# design.net
KiCad netlist of a schematic drawn in Altium Designer
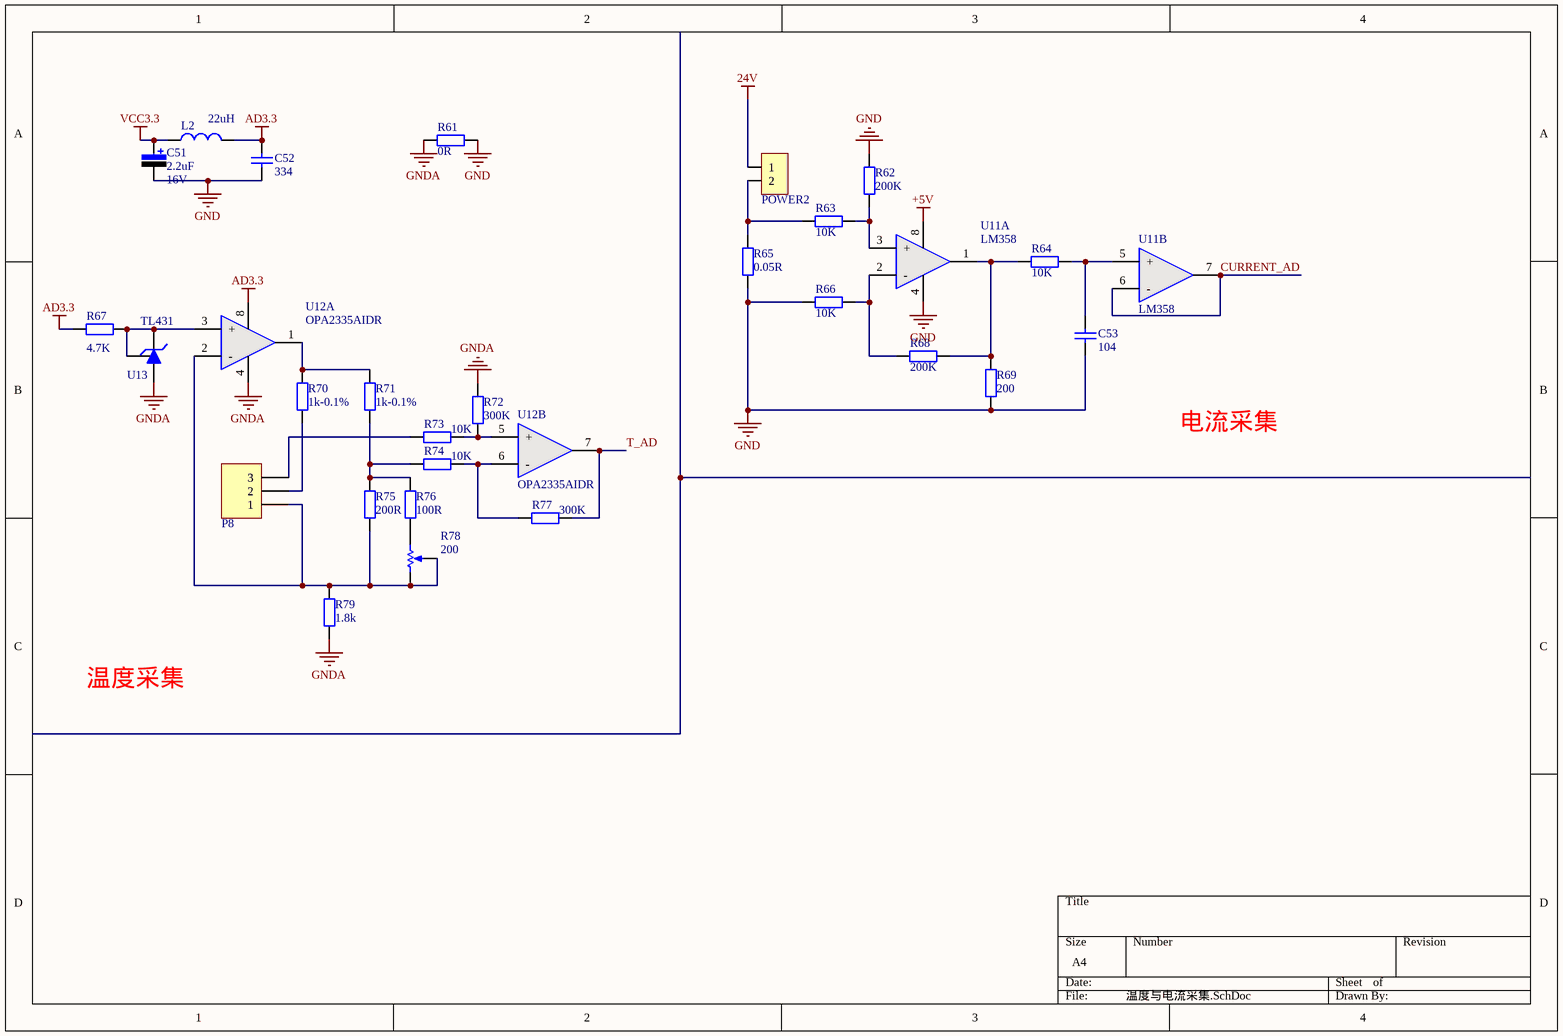
[diagram p0: 温度与电流采集.SchDoc]

(export (version "E")
  (design (tool "Eeschema 10.0.6"))
  (components
    (comp (ref "C51")
      (value "2.2uF")
      (footprint "CAP-3216")
      (description "极性电解电容")
      (fields
        (field (name "VOL") "16V")
        (field (name "Comment") "Cap Pol")
        (field (name "PUBLISHER") "Altium Limited")
      )
      (libsource (lib "Fszhang") (part "Cap Pol"))
    )
    (comp (ref "C52")
      (value "334")
      (footprint "C-RAD-0603")
      (description "无极性电容")
      (fields (field (name "Comment") "Cap") (field (name "PUBLISHER") "Altium Limited"))
      (libsource (lib "Fszhang") (part "Cap"))
    )
    (comp (ref "C53")
      (value "104")
      (footprint "C-RAD-0603")
      (description "无极性电容")
      (fields (field (name "Comment") "Cap") (field (name "PUBLISHER") "Altium Limited"))
      (libsource (lib "Fszhang") (part "Cap"))
    )
    (comp (ref "L2")
      (value "22uH")
      (footprint "0805-1")
      (description "电感")
      (fields (field (name "Comment") "Inductor") (field (name "PUBLISHER") "Altium Limited"))
      (libsource (lib "Fszhang") (part "Inductor"))
    )
    (comp (ref "P8")
      (value "Header 3")
      (footprint "XH2.54*3卧贴")
      (description "接插件")
      (fields (field (name "PUBLISHER") "Altium Limited"))
      (libsource (lib "Fszhang") (part "Header 3"))
    )
    (comp (ref "POWER2")
      (value "CNT5.08MM*2 WAN")
      (footprint "CNT5.08*2WAN")
      (libsource (lib "MY_Library") (part "CNT5.08MM*2 WAN"))
    )
    (comp (ref "R61")
      (value "0R")
      (footprint "0603-1")
      (description "贴片电阻")
      (fields (field (name "Comment") "Res1") (field (name "PUBLISHER") "Altium Limited"))
      (libsource (lib "") (part "Res1_2"))
    )
    (comp (ref "R62")
      (value "200K")
      (footprint "0603-1")
      (description "贴片电阻")
      (fields (field (name "Comment") "Res1") (field (name "PUBLISHER") "Altium Limited"))
      (libsource (lib "Fszhang") (part "Res1"))
    )
    (comp (ref "R63")
      (value "10K")
      (footprint "0603-1")
      (description "贴片电阻")
      (fields (field (name "Comment") "Res1") (field (name "PUBLISHER") "Altium Limited"))
      (libsource (lib "") (part "Res1_1"))
    )
    (comp (ref "R64")
      (value "10K")
      (footprint "0603-1")
      (description "贴片电阻")
      (fields (field (name "Comment") "Res1") (field (name "PUBLISHER") "Altium Limited"))
      (libsource (lib "") (part "Res1_2"))
    )
    (comp (ref "R65")
      (value "0.05R")
      (footprint "1*8*50mR")
      (description "贴片电阻")
      (fields (field (name "Comment") "Res1") (field (name "PUBLISHER") "Altium Limited"))
      (libsource (lib "Fszhang") (part "Res1"))
    )
    (comp (ref "R66")
      (value "10K")
      (footprint "0603-1")
      (description "贴片电阻")
      (fields (field (name "Comment") "Res1") (field (name "PUBLISHER") "Altium Limited"))
      (libsource (lib "") (part "Res1_1"))
    )
    (comp (ref "R67")
      (value "4.7K")
      (footprint "0603-1")
      (description "贴片电阻")
      (fields (field (name "Comment") "Res1") (field (name "PUBLISHER") "Altium Limited"))
      (libsource (lib "") (part "Res1_1"))
    )
    (comp (ref "R68")
      (value "200K")
      (footprint "0603-1")
      (description "贴片电阻")
      (fields (field (name "Comment") "Res1") (field (name "PUBLISHER") "Altium Limited"))
      (libsource (lib "") (part "Res1_2"))
    )
    (comp (ref "R69")
      (value "200")
      (footprint "0603-1")
      (description "贴片电阻")
      (fields (field (name "Comment") "Res1") (field (name "PUBLISHER") "Altium Limited"))
      (libsource (lib "Fszhang") (part "Res1"))
    )
    (comp (ref "R70")
      (value "1k-0.1%")
      (footprint "0603-1")
      (description "贴片电阻")
      (fields (field (name "Comment") "Res1") (field (name "PUBLISHER") "Altium Limited"))
      (libsource (lib "Fszhang") (part "Res1"))
    )
    (comp (ref "R71")
      (value "1k-0.1%")
      (footprint "0603-1")
      (description "贴片电阻")
      (fields (field (name "Comment") "Res1") (field (name "PUBLISHER") "Altium Limited"))
      (libsource (lib "Fszhang") (part "Res1"))
    )
    (comp (ref "R72")
      (value "300K")
      (footprint "0603-1")
      (description "贴片电阻")
      (fields (field (name "Comment") "Res1") (field (name "PUBLISHER") "Altium Limited"))
      (libsource (lib "Fszhang") (part "Res1"))
    )
    (comp (ref "R73")
      (value "10K")
      (footprint "0603-1")
      (description "贴片电阻")
      (fields (field (name "Comment") "Res1") (field (name "PUBLISHER") "Altium Limited"))
      (libsource (lib "") (part "Res1_1"))
    )
    (comp (ref "R74")
      (value "10K")
      (footprint "0603-1")
      (description "贴片电阻")
      (fields (field (name "Comment") "Res1") (field (name "PUBLISHER") "Altium Limited"))
      (libsource (lib "") (part "Res1_1"))
    )
    (comp (ref "R75")
      (value "200R")
      (footprint "0603-1")
      (description "贴片电阻")
      (fields (field (name "Comment") "Res1") (field (name "PUBLISHER") "Altium Limited"))
      (libsource (lib "Fszhang") (part "Res1"))
    )
    (comp (ref "R76")
      (value "100R")
      (footprint "0603-1")
      (description "贴片电阻")
      (fields (field (name "Comment") "Res1") (field (name "PUBLISHER") "Altium Limited"))
      (libsource (lib "Fszhang") (part "Res1"))
    )
    (comp (ref "R77")
      (value "300K")
      (footprint "0603-1")
      (description "贴片电阻")
      (fields (field (name "Comment") "Res1") (field (name "PUBLISHER") "Altium Limited"))
      (libsource (lib "") (part "Res1_1"))
    )
    (comp (ref "R78")
      (value "200")
      (footprint "VR-3266W")
      (description "精密可调电阻")
      (fields (field (name "Comment") "RPot") (field (name "PUBLISHER") "Altium Limited"))
      (libsource (lib "Fszhang") (part "RPot"))
    )
    (comp (ref "R79")
      (value "1.8k")
      (footprint "0603-1")
      (description "贴片电阻")
      (fields (field (name "Comment") "Res1") (field (name "PUBLISHER") "Altium Limited"))
      (libsource (lib "Fszhang") (part "Res1"))
    )
    (comp (ref "U11")
      (value "LM358")
      (footprint "NSO8_N")
      (description "双运放")
      (libsource (lib "Fszhang") (part "LM358"))
    )
    (comp (ref "U12")
      (value "OPA2335AIDR")
      (footprint "NSO8_N")
      (description "双运放")
      (libsource (lib "Fszhang") (part "AD8667"))
    )
    (comp (ref "U13") (value "TL431") (footprint "SOT23") (libsource (lib "MY_Library") (part "TL431")))
  )
  (nets
    (net (code "1") (name "+5V") (class "Default")
      (node (ref "U11") (pin "8") (pinfunction "V+_8") (pintype "power_in"))
    )
    (net (code "2") (name "/CURRENT_AD") (class "Default")
      (node (ref "U11") (pin "6") (pinfunction "-_6") (pintype "passive"))
      (node (ref "U11") (pin "7") (pinfunction "OUT2_7") (pintype "passive"))
    )
    (net (code "3") (name "/T_AD") (class "Default")
      (node (ref "R77") (pin "2") (pinfunction "2_2") (pintype "passive"))
      (node (ref "U12") (pin "7") (pinfunction "OUT2_7") (pintype "passive"))
    )
    (net (code "4") (name "24V") (class "Default")
      (node (ref "POWER2") (pin "1") (pinfunction "1_1") (pintype "passive"))
    )
    (net (code "5") (name "AD3.3") (class "Default")
      (node (ref "C52") (pin "1") (pinfunction "1_1") (pintype "passive"))
      (node (ref "L2") (pin "2") (pinfunction "2_2") (pintype "passive"))
      (node (ref "R67") (pin "1") (pinfunction "1_1") (pintype "passive"))
      (node (ref "U12") (pin "8") (pinfunction "V+_8") (pintype "power_in"))
    )
    (net (code "6") (name "GND") (class "Default")
      (node (ref "C51") (pin "2") (pinfunction "2_2") (pintype "passive"))
      (node (ref "C52") (pin "2") (pinfunction "2_2") (pintype "passive"))
      (node (ref "C53") (pin "1") (pinfunction "1_1") (pintype "passive"))
      (node (ref "R61") (pin "1") (pinfunction "1_1") (pintype "passive"))
      (node (ref "R62") (pin "2") (pinfunction "2_2") (pintype "passive"))
      (node (ref "R65") (pin "1") (pinfunction "1_1") (pintype "passive"))
      (node (ref "R66") (pin "1") (pinfunction "1_1") (pintype "passive"))
      (node (ref "R69") (pin "1") (pinfunction "1_1") (pintype "passive"))
      (node (ref "U11") (pin "4") (pinfunction "V-_4") (pintype "power_in"))
    )
    (net (code "7") (name "GNDA") (class "Default")
      (node (ref "R61") (pin "2") (pinfunction "2_2") (pintype "passive"))
      (node (ref "R72") (pin "2") (pinfunction "2_2") (pintype "passive"))
      (node (ref "R79") (pin "1") (pinfunction "1_1") (pintype "passive"))
      (node (ref "U12") (pin "4") (pinfunction "V-_4") (pintype "power_in"))
      (node (ref "U13") (pin "3") (pinfunction "3_3") (pintype "passive"))
    )
    (net (code "8") (name "Net-(P8-Pad2)") (class "Default")
      (node (ref "P8") (pin "2") (pinfunction "2_2") (pintype "passive"))
      (node (ref "R70") (pin "1") (pinfunction "1_1") (pintype "passive"))
    )
    (net (code "9") (name "Net-(P8-Pad3)") (class "Default")
      (node (ref "P8") (pin "3") (pinfunction "3_3") (pintype "passive"))
      (node (ref "R73") (pin "1") (pinfunction "1_1") (pintype "passive"))
    )
    (net (code "10") (name "Net-(POWER2-Pad2)") (class "Default")
      (node (ref "POWER2") (pin "2") (pinfunction "2_2") (pintype "passive"))
      (node (ref "R63") (pin "1") (pinfunction "1_1") (pintype "passive"))
      (node (ref "R65") (pin "2") (pinfunction "2_2") (pintype "passive"))
    )
    (net (code "11") (name "Net-(R71-Pad1)") (class "Default")
      (node (ref "R71") (pin "1") (pinfunction "1_1") (pintype "passive"))
      (node (ref "R74") (pin "1") (pinfunction "1_1") (pintype "passive"))
      (node (ref "R75") (pin "2") (pinfunction "2_2") (pintype "passive"))
      (node (ref "R76") (pin "2") (pinfunction "2_2") (pintype "passive"))
    )
    (net (code "12") (name "Net-(R78-BOT)") (class "Default")
      (node (ref "R76") (pin "1") (pinfunction "1_1") (pintype "passive"))
      (node (ref "R78") (pin "3") (pinfunction "BOT_3") (pintype "passive"))
    )
    (net (code "13") (name "Net-(R78-TAP)") (class "Default")
      (node (ref "P8") (pin "1") (pinfunction "1_1") (pintype "passive"))
      (node (ref "R75") (pin "1") (pinfunction "1_1") (pintype "passive"))
      (node (ref "R78") (pin "1") (pinfunction "TOP_1") (pintype "passive"))
      (node (ref "R78") (pin "2") (pinfunction "TAP_2") (pintype "passive"))
      (node (ref "R79") (pin "2") (pinfunction "2_2") (pintype "passive"))
      (node (ref "U12") (pin "2") (pinfunction "-_2") (pintype "passive"))
    )
    (net (code "14") (name "Net-(U11A-+)") (class "Default")
      (node (ref "R62") (pin "1") (pinfunction "1_1") (pintype "passive"))
      (node (ref "R63") (pin "2") (pinfunction "2_2") (pintype "passive"))
      (node (ref "U11") (pin "3") (pinfunction "+_3") (pintype "passive"))
    )
    (net (code "15") (name "Net-(U11A--)") (class "Default")
      (node (ref "R66") (pin "2") (pinfunction "2_2") (pintype "passive"))
      (node (ref "R68") (pin "2") (pinfunction "2_2") (pintype "passive"))
      (node (ref "U11") (pin "2") (pinfunction "-_2") (pintype "passive"))
    )
    (net (code "16") (name "Net-(U11A-OUT1)") (class "Default")
      (node (ref "R64") (pin "2") (pinfunction "2_2") (pintype "passive"))
      (node (ref "R68") (pin "1") (pinfunction "1_1") (pintype "passive"))
      (node (ref "R69") (pin "2") (pinfunction "2_2") (pintype "passive"))
      (node (ref "U11") (pin "1") (pinfunction "OUT1_1") (pintype "passive"))
    )
    (net (code "17") (name "Net-(U11B-+)") (class "Default")
      (node (ref "C53") (pin "2") (pinfunction "2_2") (pintype "passive"))
      (node (ref "R64") (pin "1") (pinfunction "1_1") (pintype "passive"))
      (node (ref "U11") (pin "5") (pinfunction "+_5") (pintype "passive"))
    )
    (net (code "18") (name "Net-(U12A-+)") (class "Default")
      (node (ref "R67") (pin "2") (pinfunction "2_2") (pintype "passive"))
      (node (ref "U12") (pin "3") (pinfunction "+_3") (pintype "passive"))
      (node (ref "U13") (pin "1") (pinfunction "1_1") (pintype "passive"))
      (node (ref "U13") (pin "2") (pinfunction "2_2") (pintype "passive"))
    )
    (net (code "19") (name "Net-(U12A-OUT1)") (class "Default")
      (node (ref "R70") (pin "2") (pinfunction "2_2") (pintype "passive"))
      (node (ref "R71") (pin "2") (pinfunction "2_2") (pintype "passive"))
      (node (ref "U12") (pin "1") (pinfunction "OUT1_1") (pintype "passive"))
    )
    (net (code "20") (name "Net-(U12B-+)") (class "Default")
      (node (ref "R72") (pin "1") (pinfunction "1_1") (pintype "passive"))
      (node (ref "R73") (pin "2") (pinfunction "2_2") (pintype "passive"))
      (node (ref "U12") (pin "5") (pinfunction "+_5") (pintype "passive"))
    )
    (net (code "21") (name "Net-(U12B--)") (class "Default")
      (node (ref "R74") (pin "2") (pinfunction "2_2") (pintype "passive"))
      (node (ref "R77") (pin "1") (pinfunction "1_1") (pintype "passive"))
      (node (ref "U12") (pin "6") (pinfunction "-_6") (pintype "passive"))
    )
    (net (code "22") (name "VCC3.3") (class "Default")
      (node (ref "C51") (pin "1") (pinfunction "1_1") (pintype "passive"))
      (node (ref "L2") (pin "1") (pinfunction "1_1") (pintype "passive"))
    )
  )
)
